# RAM.net
KiCad netlist of a schematic drawn in Altium Designer
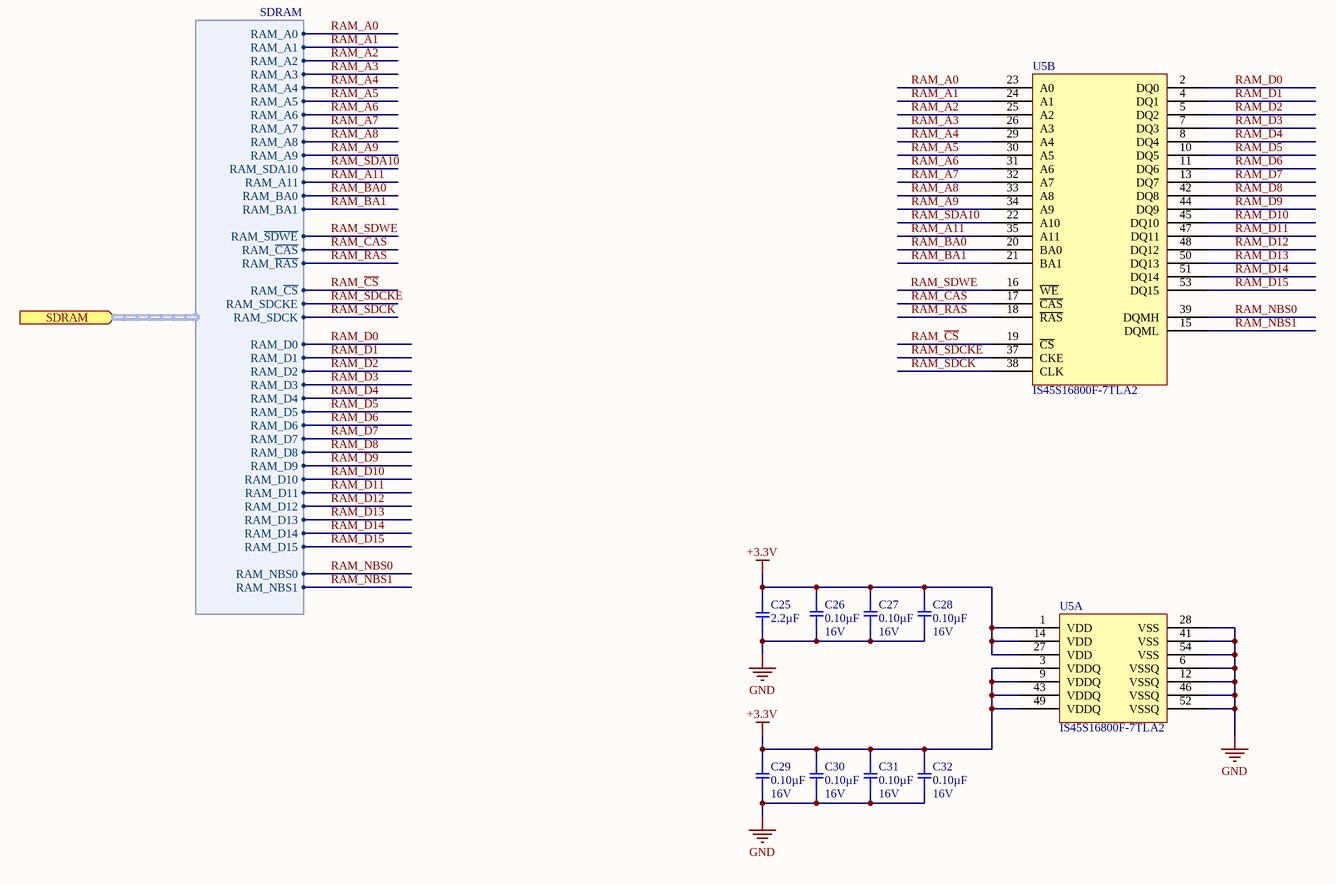
[diagram p0: RAM.SchDoc]

(export (version "E")
  (design (tool "Eeschema 10.0.6"))
  (components
    (comp (ref "C25")
      (value "2.2µF")
      (footprint "SMD-0603C")
      (description "CAP CER 2.2UF 6.3V X7R 0603")
      (fields
        (field (name "DIGI-KEY PART NUMBER") "490-5316-1-ND")
        (field (name "PART NUMBER") "GCM188R70J225KE22D")
      )
      (libsource (lib "capacitor_murata_0603") (part "GCM188R70J225KE22D"))
    )
    (comp (ref "C26")
      (value "0.10µF")
      (footprint "SMD-0402C")
      (description "CAP CER 0.1UF 16V X7R 0402")
      (fields
        (field (name "DIGI-KEY PART NUMBER") "490-4759-1-ND")
        (field (name "PART NUMBER") "GCM155R71C104KA55D")
        (field (name "VOLTAGE") "16V")
      )
      (libsource (lib "capacitor_murata_0402") (part "GCM155R71C104KA55D"))
    )
    (comp (ref "C27")
      (value "0.10µF")
      (footprint "SMD-0402C")
      (description "CAP CER 0.1UF 16V X7R 0402")
      (fields
        (field (name "DIGI-KEY PART NUMBER") "490-4759-1-ND")
        (field (name "PART NUMBER") "GCM155R71C104KA55D")
        (field (name "VOLTAGE") "16V")
      )
      (libsource (lib "capacitor_murata_0402") (part "GCM155R71C104KA55D"))
    )
    (comp (ref "C28")
      (value "0.10µF")
      (footprint "SMD-0402C")
      (description "CAP CER 0.1UF 16V X7R 0402")
      (fields
        (field (name "DIGI-KEY PART NUMBER") "490-4759-1-ND")
        (field (name "PART NUMBER") "GCM155R71C104KA55D")
        (field (name "VOLTAGE") "16V")
      )
      (libsource (lib "capacitor_murata_0402") (part "GCM155R71C104KA55D"))
    )
    (comp (ref "C29")
      (value "0.10µF")
      (footprint "SMD-0402C")
      (description "CAP CER 0.1UF 16V X7R 0402")
      (fields
        (field (name "DIGI-KEY PART NUMBER") "490-4759-1-ND")
        (field (name "PART NUMBER") "GCM155R71C104KA55D")
        (field (name "VOLTAGE") "16V")
      )
      (libsource (lib "capacitor_murata_0402") (part "GCM155R71C104KA55D"))
    )
    (comp (ref "C30")
      (value "0.10µF")
      (footprint "SMD-0402C")
      (description "CAP CER 0.1UF 16V X7R 0402")
      (fields
        (field (name "DIGI-KEY PART NUMBER") "490-4759-1-ND")
        (field (name "PART NUMBER") "GCM155R71C104KA55D")
        (field (name "VOLTAGE") "16V")
      )
      (libsource (lib "capacitor_murata_0402") (part "GCM155R71C104KA55D"))
    )
    (comp (ref "C31")
      (value "0.10µF")
      (footprint "SMD-0402C")
      (description "CAP CER 0.1UF 16V X7R 0402")
      (fields
        (field (name "DIGI-KEY PART NUMBER") "490-4759-1-ND")
        (field (name "PART NUMBER") "GCM155R71C104KA55D")
        (field (name "VOLTAGE") "16V")
      )
      (libsource (lib "capacitor_murata_0402") (part "GCM155R71C104KA55D"))
    )
    (comp (ref "C32")
      (value "0.10µF")
      (footprint "SMD-0402C")
      (description "CAP CER 0.1UF 16V X7R 0402")
      (fields
        (field (name "DIGI-KEY PART NUMBER") "490-4759-1-ND")
        (field (name "PART NUMBER") "GCM155R71C104KA55D")
        (field (name "VOLTAGE") "16V")
      )
      (libsource (lib "capacitor_murata_0402") (part "GCM155R71C104KA55D"))
    )
    (comp (ref "U5")
      (value "IS45S16800F-7TLA2")
      (footprint "TSOP80P1180X120-54N")
      (libsource (lib "ModularPayload") (part "IS45S16800F-7TLA2"))
    )
  )
  (nets
    (net (code "2") (name "+3.3V") (class "Default")
      (node (ref "C25") (pin "1") (pinfunction "1_1") (pintype "passive"))
      (node (ref "C26") (pin "2") (pinfunction "2_2") (pintype "passive"))
      (node (ref "C27") (pin "2") (pinfunction "2_2") (pintype "passive"))
      (node (ref "C28") (pin "2") (pinfunction "2_2") (pintype "passive"))
      (node (ref "C29") (pin "2") (pinfunction "2_2") (pintype "passive"))
      (node (ref "C30") (pin "2") (pinfunction "2_2") (pintype "passive"))
      (node (ref "C31") (pin "2") (pinfunction "2_2") (pintype "passive"))
      (node (ref "C32") (pin "2") (pinfunction "2_2") (pintype "passive"))
      (node (ref "U5") (pin "1") (pinfunction "VDD_1") (pintype "passive"))
      (node (ref "U5") (pin "14") (pinfunction "VDD_14") (pintype "passive"))
      (node (ref "U5") (pin "27") (pinfunction "VDD_27") (pintype "passive"))
      (node (ref "U5") (pin "3") (pinfunction "VDDQ_3") (pintype "passive"))
      (node (ref "U5") (pin "43") (pinfunction "VDDQ_43") (pintype "passive"))
      (node (ref "U5") (pin "49") (pinfunction "VDDQ_49") (pintype "passive"))
      (node (ref "U5") (pin "9") (pinfunction "VDDQ_9") (pintype "passive"))
    )
    (net (code "3") (name "/RAM_A0") (class "Default")
      (node (ref "U5") (pin "23") (pinfunction "A0_23") (pintype "passive"))
    )
    (net (code "4") (name "/RAM_A1") (class "Default")
      (node (ref "U5") (pin "24") (pinfunction "A1_24") (pintype "passive"))
    )
    (net (code "5") (name "/RAM_A2") (class "Default")
      (node (ref "U5") (pin "25") (pinfunction "A2_25") (pintype "passive"))
    )
    (net (code "6") (name "/RAM_A3") (class "Default")
      (node (ref "U5") (pin "26") (pinfunction "A3_26") (pintype "passive"))
    )
    (net (code "7") (name "/RAM_A4") (class "Default")
      (node (ref "U5") (pin "29") (pinfunction "A4_29") (pintype "passive"))
    )
    (net (code "8") (name "/RAM_A5") (class "Default")
      (node (ref "U5") (pin "30") (pinfunction "A5_30") (pintype "passive"))
    )
    (net (code "9") (name "/RAM_A6") (class "Default")
      (node (ref "U5") (pin "31") (pinfunction "A6_31") (pintype "passive"))
    )
    (net (code "10") (name "/RAM_A7") (class "Default")
      (node (ref "U5") (pin "32") (pinfunction "A7_32") (pintype "passive"))
    )
    (net (code "11") (name "/RAM_A8") (class "Default")
      (node (ref "U5") (pin "33") (pinfunction "A8_33") (pintype "passive"))
    )
    (net (code "12") (name "/RAM_A9") (class "Default")
      (node (ref "U5") (pin "34") (pinfunction "A9_34") (pintype "passive"))
    )
    (net (code "13") (name "/RAM_A11") (class "Default")
      (node (ref "U5") (pin "35") (pinfunction "A11_35") (pintype "passive"))
    )
    (net (code "14") (name "/RAM_BA0") (class "Default")
      (node (ref "U5") (pin "20") (pinfunction "BA0_20") (pintype "passive"))
    )
    (net (code "15") (name "/RAM_BA1") (class "Default")
      (node (ref "U5") (pin "21") (pinfunction "BA1_21") (pintype "passive"))
    )
    (net (code "16") (name "/RAM_CAS") (class "Default")
      (node (ref "U5") (pin "17") (pinfunction "~{CAS}_17") (pintype "passive"))
    )
    (net (code "17") (name "/RAM_D0") (class "Default")
      (node (ref "U5") (pin "2") (pinfunction "DQ0_2") (pintype "passive"))
    )
    (net (code "18") (name "/RAM_D1") (class "Default")
      (node (ref "U5") (pin "4") (pinfunction "DQ1_4") (pintype "passive"))
    )
    (net (code "19") (name "/RAM_D2") (class "Default")
      (node (ref "U5") (pin "5") (pinfunction "DQ2_5") (pintype "passive"))
    )
    (net (code "20") (name "/RAM_D3") (class "Default")
      (node (ref "U5") (pin "7") (pinfunction "DQ3_7") (pintype "passive"))
    )
    (net (code "21") (name "/RAM_D4") (class "Default")
      (node (ref "U5") (pin "8") (pinfunction "DQ4_8") (pintype "passive"))
    )
    (net (code "22") (name "/RAM_D5") (class "Default")
      (node (ref "U5") (pin "10") (pinfunction "DQ5_10") (pintype "passive"))
    )
    (net (code "23") (name "/RAM_D6") (class "Default")
      (node (ref "U5") (pin "11") (pinfunction "DQ6_11") (pintype "passive"))
    )
    (net (code "24") (name "/RAM_D7") (class "Default")
      (node (ref "U5") (pin "13") (pinfunction "DQ7_13") (pintype "passive"))
    )
    (net (code "25") (name "/RAM_D8") (class "Default")
      (node (ref "U5") (pin "42") (pinfunction "DQ8_42") (pintype "passive"))
    )
    (net (code "26") (name "/RAM_D9") (class "Default")
      (node (ref "U5") (pin "44") (pinfunction "DQ9_44") (pintype "passive"))
    )
    (net (code "27") (name "/RAM_D10") (class "Default")
      (node (ref "U5") (pin "45") (pinfunction "DQ10_45") (pintype "passive"))
    )
    (net (code "28") (name "/RAM_D11") (class "Default")
      (node (ref "U5") (pin "47") (pinfunction "DQ11_47") (pintype "passive"))
    )
    (net (code "29") (name "/RAM_D12") (class "Default")
      (node (ref "U5") (pin "48") (pinfunction "DQ12_48") (pintype "passive"))
    )
    (net (code "30") (name "/RAM_D13") (class "Default")
      (node (ref "U5") (pin "50") (pinfunction "DQ13_50") (pintype "passive"))
    )
    (net (code "31") (name "/RAM_D14") (class "Default")
      (node (ref "U5") (pin "51") (pinfunction "DQ14_51") (pintype "passive"))
    )
    (net (code "32") (name "/RAM_D15") (class "Default")
      (node (ref "U5") (pin "53") (pinfunction "DQ15_53") (pintype "passive"))
    )
    (net (code "33") (name "/RAM_NBS0") (class "Default")
      (node (ref "U5") (pin "39") (pinfunction "DQMH_39") (pintype "passive"))
    )
    (net (code "34") (name "/RAM_NBS1") (class "Default")
      (node (ref "U5") (pin "15") (pinfunction "DQML_15") (pintype "passive"))
    )
    (net (code "35") (name "/RAM_RAS") (class "Default")
      (node (ref "U5") (pin "18") (pinfunction "~{RAS}_18") (pintype "passive"))
    )
    (net (code "36") (name "/RAM_SDA10") (class "Default")
      (node (ref "U5") (pin "22") (pinfunction "A10_22") (pintype "passive"))
    )
    (net (code "37") (name "/RAM_SDCK") (class "Default")
      (node (ref "U5") (pin "38") (pinfunction "CLK_38") (pintype "passive"))
    )
    (net (code "38") (name "/RAM_SDCKE") (class "Default")
      (node (ref "U5") (pin "37") (pinfunction "CKE_37") (pintype "passive"))
    )
    (net (code "39") (name "/RAM_SDWE") (class "Default")
      (node (ref "U5") (pin "16") (pinfunction "~{WE}_16") (pintype "passive"))
    )
    (net (code "40") (name "/RAM_~{CS}") (class "Default")
      (node (ref "U5") (pin "19") (pinfunction "~{CS}_19") (pintype "passive"))
    )
    (net (code "42") (name "GND") (class "Default")
      (node (ref "C25") (pin "2") (pinfunction "2_2") (pintype "passive"))
      (node (ref "C26") (pin "1") (pinfunction "1_1") (pintype "passive"))
      (node (ref "C27") (pin "1") (pinfunction "1_1") (pintype "passive"))
      (node (ref "C28") (pin "1") (pinfunction "1_1") (pintype "passive"))
      (node (ref "C29") (pin "1") (pinfunction "1_1") (pintype "passive"))
      (node (ref "C30") (pin "1") (pinfunction "1_1") (pintype "passive"))
      (node (ref "C31") (pin "1") (pinfunction "1_1") (pintype "passive"))
      (node (ref "C32") (pin "1") (pinfunction "1_1") (pintype "passive"))
      (node (ref "U5") (pin "12") (pinfunction "VSSQ_12") (pintype "passive"))
      (node (ref "U5") (pin "28") (pinfunction "VSS_28") (pintype "passive"))
      (node (ref "U5") (pin "41") (pinfunction "VSS_41") (pintype "passive"))
      (node (ref "U5") (pin "46") (pinfunction "VSSQ_46") (pintype "passive"))
      (node (ref "U5") (pin "52") (pinfunction "VSSQ_52") (pintype "passive"))
      (node (ref "U5") (pin "54") (pinfunction "VSS_54") (pintype "passive"))
      (node (ref "U5") (pin "6") (pinfunction "VSSQ_6") (pintype "passive"))
    )
  )
)
